# System.net
KiCad netlist of a schematic drawn in Altium Designer
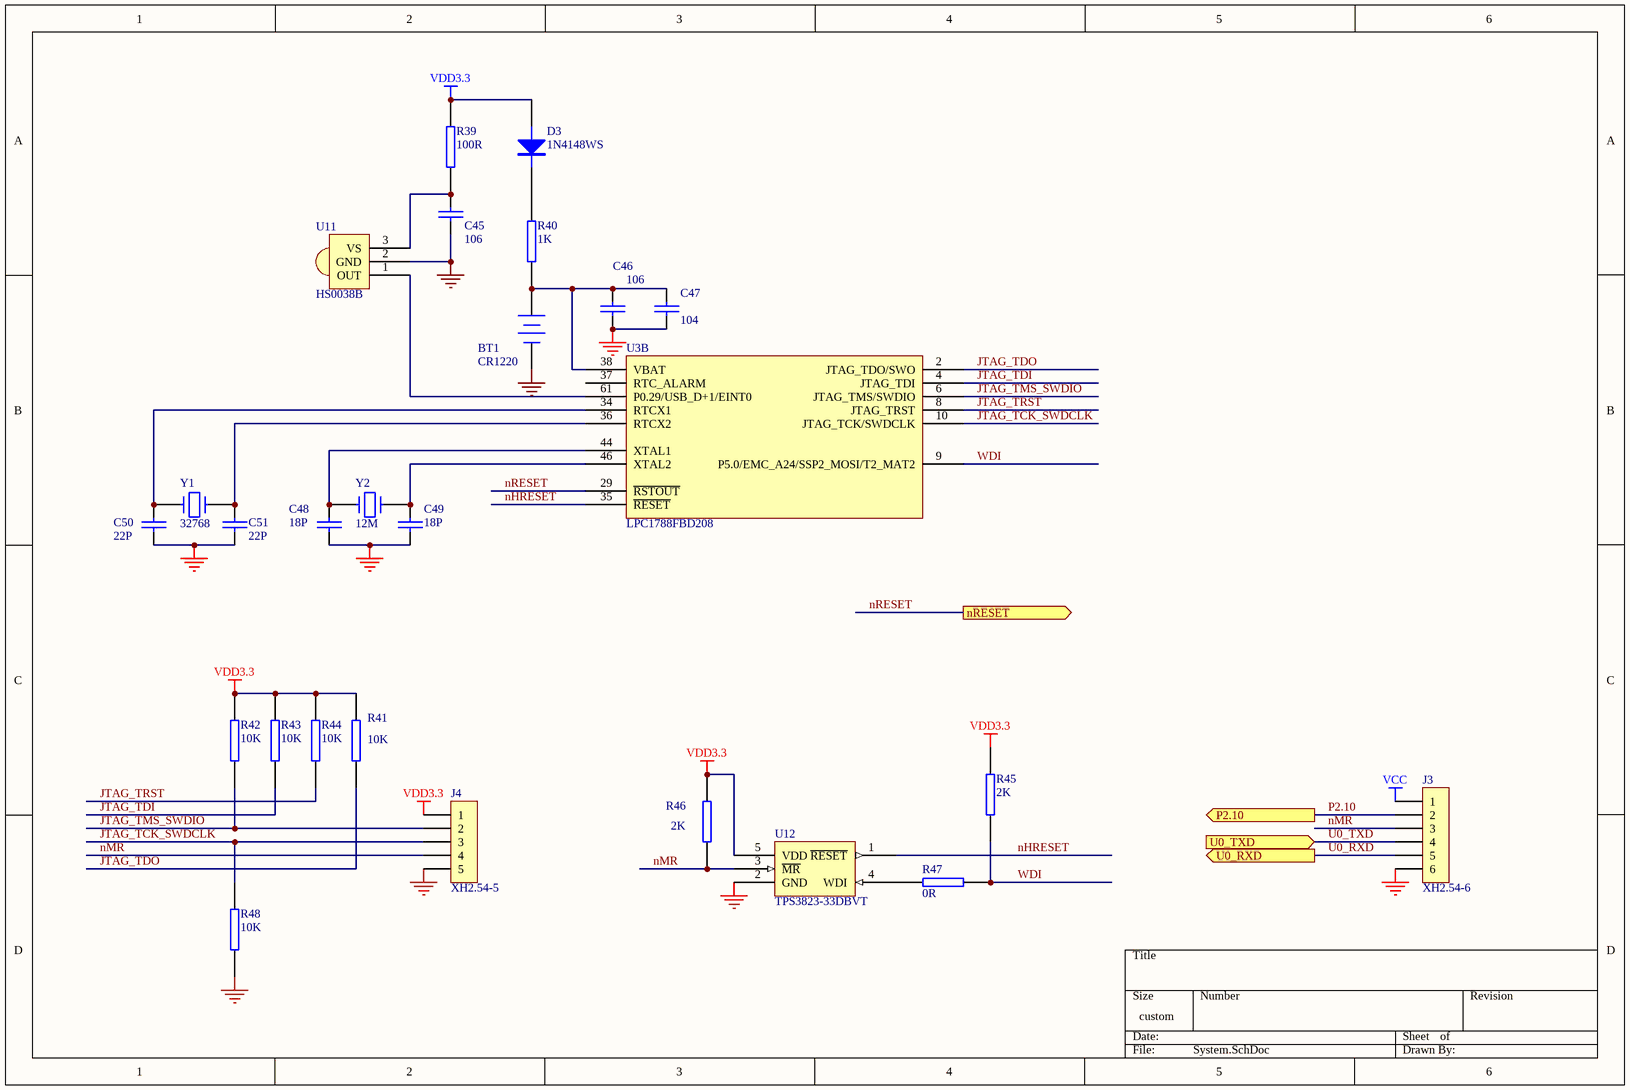
[diagram p0: System.SchDoc]

(export (version "E")
  (design (tool "Eeschema 10.0.6"))
  (components
    (comp (ref "BT1")
      (value "CR1220")
      (footprint "CR1220")
      (description "Multicell Battery")
      (fields (field (name "PUBLISHER") "Altium Limited"))
      (libsource (lib "Miscellaneous Devices") (part "Battery"))
    )
    (comp (ref "C45")
      (value "106")
      (footprint "C0603")
      (description "Capacitor")
      (libsource (lib "*") (part "CAP"))
    )
    (comp (ref "C46")
      (value "106")
      (footprint "C0603")
      (description "Capacitor")
      (libsource (lib "*") (part "CAP"))
    )
    (comp (ref "C47")
      (value "104")
      (footprint "C0603")
      (description "Capacitor")
      (libsource (lib "*") (part "CAP"))
    )
    (comp (ref "C48")
      (value "18P")
      (footprint "C0603")
      (description "Capacitor")
      (libsource (lib "*") (part "CAP"))
    )
    (comp (ref "C49")
      (value "18P")
      (footprint "C0603")
      (description "Capacitor")
      (libsource (lib "*") (part "CAP"))
    )
    (comp (ref "C50")
      (value "22P")
      (footprint "C0603")
      (description "Capacitor")
      (libsource (lib "*") (part "CAP"))
    )
    (comp (ref "C51")
      (value "22P")
      (footprint "C0603")
      (description "Capacitor")
      (libsource (lib "*") (part "CAP"))
    )
    (comp (ref "D3")
      (value "1N4148WS")
      (footprint "SOD323")
      (description "Diode")
      (libsource (lib "*") (part "DIODE"))
    )
    (comp (ref "J3")
      (value "XH2.54-6")
      (footprint "A2501WF-06A")
      (libsource (lib "LPC1788") (part "XH2.54-6-SMD"))
    )
    (comp (ref "J4")
      (value "XH2.54-5")
      (footprint "A2501WF-05A")
      (libsource (lib "LPC1788") (part "XH2.54-5-SMD"))
    )
    (comp (ref "R39") (value "100R") (footprint "R0603") (libsource (lib "*") (part "RES2")))
    (comp (ref "R40") (value "1K") (footprint "R0603") (libsource (lib "LPC1788") (part "RES2")))
    (comp (ref "R41") (value "10K") (footprint "R0603") (libsource (lib "*") (part "RES2")))
    (comp (ref "R42") (value "10K") (footprint "R0603") (libsource (lib "*") (part "RES2")))
    (comp (ref "R43") (value "10K") (footprint "R0603") (libsource (lib "*") (part "RES2")))
    (comp (ref "R44") (value "10K") (footprint "R0603") (libsource (lib "*") (part "RES2")))
    (comp (ref "R45") (value "2K") (footprint "R0603") (libsource (lib "*") (part "RES2")))
    (comp (ref "R46") (value "2K") (footprint "R0603") (libsource (lib "*") (part "RES2")))
    (comp (ref "R47") (value "0R") (footprint "R0603") (libsource (lib "*") (part "RES2")))
    (comp (ref "R48") (value "10K") (footprint "R0603") (libsource (lib "*") (part "RES2")))
    (comp (ref "U3")
      (value "LPC1788FBD208")
      (footprint "QFP208")
      (libsource (lib "LPC1788") (part "LPC1788FBD208"))
    )
    (comp (ref "U11") (value "HS0038B") (footprint "HS0038B") (libsource (lib "LPC1788") (part "HS0038B")))
    (comp (ref "U12")
      (value "TPS3823-33DBVT")
      (footprint "TSOP-5")
      (libsource (lib "*") (part "TPS3823-33DBVT"))
    )
    (comp (ref "Y1")
      (value "32768")
      (footprint "MC-306")
      (description "Crystal")
      (libsource (lib "*") (part "CRYSTAL"))
    )
    (comp (ref "Y2")
      (value "12M")
      (footprint "CY5032")
      (description "Crystal")
      (libsource (lib "*") (part "CRYSTAL"))
    )
  )
  (nets
    (net (code "1") (name "/JTAG_TCK_SWDCLK") (class "Default")
      (node (ref "J4") (pin "3") (pinfunction "3_3") (pintype "passive"))
      (node (ref "R48") (pin "2") (pinfunction "2_2") (pintype "passive"))
      (node (ref "U3") (pin "10") (pinfunction "JTAG_TCK/SWDCLK_10") (pintype "passive"))
    )
    (net (code "2") (name "/JTAG_TDI") (class "Default")
      (node (ref "R43") (pin "1") (pinfunction "1_1") (pintype "passive"))
      (node (ref "U3") (pin "4") (pinfunction "JTAG_TDI_4") (pintype "passive"))
    )
    (net (code "3") (name "/JTAG_TDO") (class "Default")
      (node (ref "R41") (pin "1") (pinfunction "1_1") (pintype "passive"))
      (node (ref "U3") (pin "2") (pinfunction "JTAG_TDO/SWO_2") (pintype "passive"))
    )
    (net (code "4") (name "/JTAG_TMS_SWDIO") (class "Default")
      (node (ref "J4") (pin "2") (pinfunction "2_2") (pintype "passive"))
      (node (ref "R42") (pin "1") (pinfunction "1_1") (pintype "passive"))
      (node (ref "U3") (pin "6") (pinfunction "JTAG_TMS/SWDIO_6") (pintype "passive"))
    )
    (net (code "5") (name "/JTAG_TRST") (class "Default")
      (node (ref "R44") (pin "1") (pinfunction "1_1") (pintype "passive"))
      (node (ref "U3") (pin "8") (pinfunction "JTAG_TRST_8") (pintype "passive"))
    )
    (net (code "6") (name "/P2.10") (class "Default")
      (node (ref "J3") (pin "2") (pinfunction "2_2") (pintype "passive"))
    )
    (net (code "7") (name "/U0_RXD") (class "Default")
      (node (ref "J3") (pin "5") (pinfunction "5_5") (pintype "passive"))
    )
    (net (code "8") (name "/U0_TXD") (class "Default")
      (node (ref "J3") (pin "4") (pinfunction "4_4") (pintype "passive"))
    )
    (net (code "9") (name "/WDI") (class "Default")
      (node (ref "R45") (pin "1") (pinfunction "1_1") (pintype "passive"))
      (node (ref "R47") (pin "2") (pinfunction "2_2") (pintype "passive"))
      (node (ref "U3") (pin "9") (pinfunction "P5.0/EMC_A24/SSP2_MOSI/T2_MAT2_9") (pintype "passive"))
    )
    (net (code "10") (name "/nHRESET") (class "Default")
      (node (ref "U12") (pin "1") (pinfunction "~{RESET}_1") (pintype "output"))
      (node (ref "U3") (pin "35") (pinfunction "~{RESET}_35") (pintype "passive"))
    )
    (net (code "11") (name "/nMR") (class "Default")
      (node (ref "J3") (pin "3") (pinfunction "3_3") (pintype "passive"))
      (node (ref "J4") (pin "4") (pinfunction "4_4") (pintype "passive"))
      (node (ref "R46") (pin "1") (pinfunction "1_1") (pintype "passive"))
      (node (ref "U12") (pin "3") (pinfunction "~{MR}_3") (pintype "input"))
    )
    (net (code "12") (name "/nRESET") (class "Default")
      (node (ref "U3") (pin "29") (pinfunction "~{RSTOUT}_29") (pintype "passive"))
    )
    (net (code "13") (name "GND") (class "Default")
      (node (ref "BT1") (pin "2") (pinfunction "-_2") (pintype "passive"))
      (node (ref "C45") (pin "2") (pinfunction "2_2") (pintype "passive"))
      (node (ref "C46") (pin "2") (pinfunction "2_2") (pintype "passive"))
      (node (ref "C47") (pin "2") (pinfunction "2_2") (pintype "passive"))
      (node (ref "C48") (pin "2") (pinfunction "2_2") (pintype "passive"))
      (node (ref "C49") (pin "2") (pinfunction "2_2") (pintype "passive"))
      (node (ref "C50") (pin "2") (pinfunction "2_2") (pintype "passive"))
      (node (ref "C51") (pin "2") (pinfunction "2_2") (pintype "passive"))
      (node (ref "J3") (pin "6") (pinfunction "6_6") (pintype "passive"))
      (node (ref "J4") (pin "5") (pinfunction "5_5") (pintype "passive"))
      (node (ref "R48") (pin "1") (pinfunction "1_1") (pintype "passive"))
      (node (ref "U11") (pin "2") (pinfunction "GND_2") (pintype "passive"))
      (node (ref "U12") (pin "2") (pinfunction "GND_2") (pintype "power_in"))
    )
    (net (code "14") (name "Net-(BT1-+)") (class "Default")
      (node (ref "BT1") (pin "1") (pinfunction "+_1") (pintype "passive"))
      (node (ref "C46") (pin "1") (pinfunction "1_1") (pintype "passive"))
      (node (ref "C47") (pin "1") (pinfunction "1_1") (pintype "passive"))
      (node (ref "R40") (pin "2") (pinfunction "2_2") (pintype "passive"))
      (node (ref "U3") (pin "38") (pinfunction "VBAT_38") (pintype "passive"))
    )
    (net (code "15") (name "Net-(D3-K)") (class "Default")
      (node (ref "D3") (pin "2") (pinfunction "K_2") (pintype "passive"))
      (node (ref "R40") (pin "1") (pinfunction "1_1") (pintype "passive"))
    )
    (net (code "16") (name "Net-(U3B-RTCX1)") (class "Default")
      (node (ref "C50") (pin "1") (pinfunction "1_1") (pintype "passive"))
      (node (ref "U3") (pin "34") (pinfunction "RTCX1_34") (pintype "passive"))
      (node (ref "Y1") (pin "2") (pinfunction "2_2") (pintype "passive"))
    )
    (net (code "17") (name "Net-(U3B-RTCX2)") (class "Default")
      (node (ref "C51") (pin "1") (pinfunction "1_1") (pintype "passive"))
      (node (ref "U3") (pin "36") (pinfunction "RTCX2_36") (pintype "passive"))
      (node (ref "Y1") (pin "1") (pinfunction "1_1") (pintype "passive"))
    )
    (net (code "18") (name "Net-(U3B-XTAL1)") (class "Default")
      (node (ref "C48") (pin "1") (pinfunction "1_1") (pintype "passive"))
      (node (ref "U3") (pin "44") (pinfunction "XTAL1_44") (pintype "passive"))
      (node (ref "Y2") (pin "1") (pinfunction "1_1") (pintype "passive"))
    )
    (net (code "19") (name "Net-(U3B-XTAL2)") (class "Default")
      (node (ref "C49") (pin "1") (pinfunction "1_1") (pintype "passive"))
      (node (ref "U3") (pin "46") (pinfunction "XTAL2_46") (pintype "passive"))
      (node (ref "Y2") (pin "2") (pinfunction "2_2") (pintype "passive"))
    )
    (net (code "20") (name "Net-(U11-OUT)") (class "Default")
      (node (ref "U11") (pin "1") (pinfunction "OUT_1") (pintype "passive"))
      (node (ref "U3") (pin "61") (pinfunction "P0.29/USB_D+1/EINT0_61") (pintype "passive"))
    )
    (net (code "21") (name "Net-(U11-VS)") (class "Default")
      (node (ref "C45") (pin "1") (pinfunction "1_1") (pintype "passive"))
      (node (ref "R39") (pin "1") (pinfunction "1_1") (pintype "passive"))
      (node (ref "U11") (pin "3") (pinfunction "VS_3") (pintype "passive"))
    )
    (net (code "22") (name "Net-(U12-WDI)") (class "Default")
      (node (ref "R47") (pin "1") (pinfunction "1_1") (pintype "passive"))
      (node (ref "U12") (pin "4") (pinfunction "WDI_4") (pintype "input"))
    )
    (net (code "23") (name "VCC") (class "Default")
      (node (ref "J3") (pin "1") (pinfunction "1_1") (pintype "passive"))
    )
    (net (code "24") (name "VDD3.3") (class "Default")
      (node (ref "D3") (pin "1") (pinfunction "A_1") (pintype "passive"))
      (node (ref "J4") (pin "1") (pinfunction "1_1") (pintype "passive"))
      (node (ref "R39") (pin "2") (pinfunction "2_2") (pintype "passive"))
      (node (ref "R41") (pin "2") (pinfunction "2_2") (pintype "passive"))
      (node (ref "R42") (pin "2") (pinfunction "2_2") (pintype "passive"))
      (node (ref "R43") (pin "2") (pinfunction "2_2") (pintype "passive"))
      (node (ref "R44") (pin "2") (pinfunction "2_2") (pintype "passive"))
      (node (ref "R45") (pin "2") (pinfunction "2_2") (pintype "passive"))
      (node (ref "R46") (pin "2") (pinfunction "2_2") (pintype "passive"))
      (node (ref "U12") (pin "5") (pinfunction "VDD_5") (pintype "power_in"))
    )
    (net (code "25") (name "unconnected-(U3B-RTC_ALARM-Pad37)") (class "Default")
      (node (ref "U3") (pin "37") (pinfunction "RTC_ALARM_37") (pintype "passive"))
    )
  )
)
